# 9_arduinoConnectors.net
KiCad netlist of a schematic drawn in Altium Designer
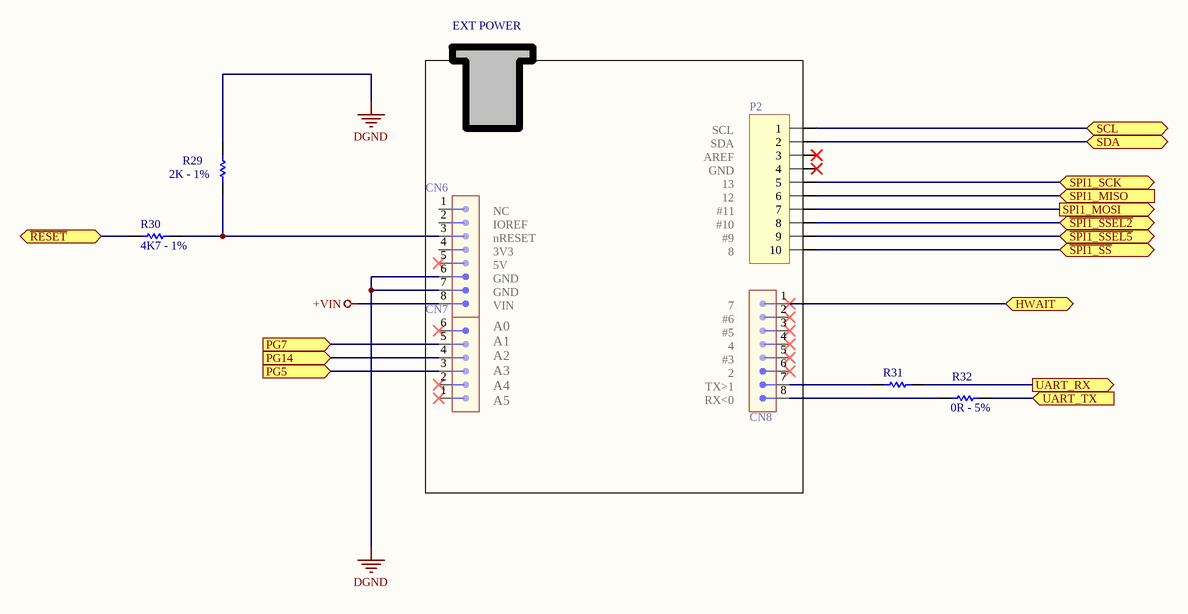
[diagram p0: 9_arduinoConnectors.SchDoc]

(export (version "E")
  (design (tool "Eeschema 10.0.6"))
  (components
    (comp (ref "CN6")
      (value "Conector M HEADER, 180G, SIMPLES, 8P")
      (footprint "BLKCON.100/MCS-8/W.100/8")
      (fields (field (name "MANUFACTURER") "METALTEX") (field (name "PARTNUMBER") "MCS-08"))
      (libsource (lib "") (part "CNC M HEADER, 180G, SIMPLES, 8P - 786_1"))
    )
    (comp (ref "CN7")
      (value "Conector M HEADER, 180G, SIMPLES, 6P")
      (footprint "BLKCON.100/MCS-6/W.100/6")
      (fields (field (name "MANUFACTURER") "METALTEX") (field (name "PARTNUMBER") "MCS-06"))
      (libsource (lib "Conector") (part "CNC M HEADER, 180G, SIMPLES, 6P - 785"))
    )
    (comp (ref "CN8")
      (value "Conector M HEADER, 180G, SIMPLES, 8P")
      (footprint "BLKCON.100/MCS-8/W.100/8")
      (fields (field (name "MANUFACTURER") "METALTEX") (field (name "PARTNUMBER") "MCS-08"))
      (libsource (lib "Conector") (part "CNC M HEADER, 180G, SIMPLES, 8P - 786"))
    )
    (comp (ref "P2")
      (value "Header 10")
      (footprint "HDR1X10")
      (description "Header, 10-Pin")
      (fields (field (name "PUBLISHER") "Altium Limited"))
      (libsource (lib "Miscellaneous Connectors") (part "Header 10"))
    )
    (comp (ref "R29")
      (value "2K - 1% - 0805 - 392")
      (footprint "SMD0805")
      (description "Resistor 2K, 1%, SMD 0805")
      (fields
        (field (name "PARTNUMBER") "0805W8F2001T5E")
        (field (name "MANUFACTURER") "SAMSUNG")
        (field (name "VALOR") "2K - 1%")
      )
      (libsource (lib "Resistor_smd") (part "2K - 1% - 0805 - 392"))
    )
    (comp (ref "R30")
      (value "4K7 - 1% - 0805 - 438")
      (footprint "SMD0805")
      (description "Resistor 4K7, 1%, SMD 0805")
      (fields
        (field (name "PARTNUMBER") "RC2012F4701CS")
        (field (name "MANUFACTURER") "SAMSUNG")
        (field (name "VALOR") "4K7 - 1%")
      )
      (libsource (lib "Resistor_smd") (part "4K7 - 1% - 0805 - 438"))
    )
    (comp (ref "R31")
      (value "0R - 5% - 0805 - 3365")
      (footprint "SMD0805")
      (description "Resistor 0R, 5%, SMD 0805")
      (fields (field (name "PARTNUMBER") "ERJ-6GEY0R00V") (field (name "MANUFACTURER") "PANASONIC"))
      (libsource (lib "Resistor_smd") (part "0R - 5% - 0805 - 3365"))
    )
    (comp (ref "R32")
      (value "0R - 5% - 0805 - 3365")
      (footprint "SMD0805")
      (description "Resistor 0R, 5%, SMD 0805")
      (fields
        (field (name "PARTNUMBER") "ERJ-6GEY0R00V")
        (field (name "MANUFACTURER") "PANASONIC")
        (field (name "VALOR") "0R - 5%")
      )
      (libsource (lib "Resistor_smd") (part "0R - 5% - 0805 - 3365"))
    )
  )
  (nets
    (net (code "1") (name "+VIN") (class "Default")
      (node (ref "CN6") (pin "8") (pinfunction "8_8") (pintype "passive"))
    )
    (net (code "2") (name "/HWAIT") (class "Default")
      (node (ref "CN8") (pin "1") (pinfunction "1_1") (pintype "passive+no_connect"))
    )
    (net (code "3") (name "/PG5") (class "Default")
      (node (ref "CN7") (pin "3") (pinfunction "3_3") (pintype "passive"))
    )
    (net (code "4") (name "/PG7") (class "Default")
      (node (ref "CN7") (pin "5") (pinfunction "5_5") (pintype "passive"))
    )
    (net (code "5") (name "/PG14") (class "Default")
      (node (ref "CN7") (pin "4") (pinfunction "4_4") (pintype "passive"))
    )
    (net (code "6") (name "/RESET") (class "Default")
      (node (ref "R30") (pin "1") (pinfunction "1_1") (pintype "passive"))
    )
    (net (code "7") (name "/SCL") (class "Default")
      (node (ref "P2") (pin "1") (pinfunction "1_1") (pintype "passive"))
    )
    (net (code "8") (name "/SDA") (class "Default")
      (node (ref "P2") (pin "2") (pinfunction "2_2") (pintype "passive"))
    )
    (net (code "9") (name "/SPI1_MISO") (class "Default")
      (node (ref "P2") (pin "6") (pinfunction "6_6") (pintype "passive"))
    )
    (net (code "10") (name "/SPI1_MOSI") (class "Default")
      (node (ref "P2") (pin "7") (pinfunction "7_7") (pintype "passive"))
    )
    (net (code "11") (name "/SPI1_SCK") (class "Default")
      (node (ref "P2") (pin "5") (pinfunction "5_5") (pintype "passive"))
    )
    (net (code "12") (name "/SPI1_SS") (class "Default")
      (node (ref "P2") (pin "10") (pinfunction "10_10") (pintype "passive"))
    )
    (net (code "13") (name "/SPI1_SSEL2") (class "Default")
      (node (ref "P2") (pin "8") (pinfunction "8_8") (pintype "passive"))
    )
    (net (code "14") (name "/SPI1_SSEL5") (class "Default")
      (node (ref "P2") (pin "9") (pinfunction "9_9") (pintype "passive"))
    )
    (net (code "15") (name "/UART_RX") (class "Default")
      (node (ref "R31") (pin "2") (pinfunction "2_2") (pintype "passive"))
    )
    (net (code "16") (name "/UART_TX") (class "Default")
      (node (ref "R32") (pin "2") (pinfunction "2_2") (pintype "passive"))
    )
    (net (code "17") (name "DGND") (class "Default")
      (node (ref "CN6") (pin "6") (pinfunction "6_6") (pintype "passive"))
      (node (ref "CN6") (pin "7") (pinfunction "7_7") (pintype "passive"))
      (node (ref "R29") (pin "2") (pinfunction "2_2") (pintype "passive"))
    )
    (net (code "18") (name "Net-(CN6-Pad3)") (class "Default")
      (node (ref "CN6") (pin "3") (pinfunction "3_3") (pintype "passive"))
      (node (ref "R29") (pin "1") (pinfunction "1_1") (pintype "passive"))
      (node (ref "R30") (pin "2") (pinfunction "2_2") (pintype "passive"))
    )
    (net (code "19") (name "Net-(CN8-Pad7)") (class "Default")
      (node (ref "CN8") (pin "7") (pinfunction "7_7") (pintype "passive"))
      (node (ref "R31") (pin "1") (pinfunction "1_1") (pintype "passive"))
    )
    (net (code "20") (name "Net-(CN8-Pad8)") (class "Default")
      (node (ref "CN8") (pin "8") (pinfunction "8_8") (pintype "passive"))
      (node (ref "R32") (pin "1") (pinfunction "1_1") (pintype "passive"))
    )
    (net (code "21") (name "unconnected-(CN6-Pad1)") (class "Default")
      (node (ref "CN6") (pin "1") (pinfunction "1_1") (pintype "passive"))
    )
    (net (code "22") (name "unconnected-(CN6-Pad2)") (class "Default")
      (node (ref "CN6") (pin "2") (pinfunction "2_2") (pintype "passive"))
    )
    (net (code "23") (name "unconnected-(CN6-Pad4)") (class "Default")
      (node (ref "CN6") (pin "4") (pinfunction "4_4") (pintype "passive"))
    )
    (net (code "24") (name "unconnected-(CN6-Pad5)") (class "Default")
      (node (ref "CN6") (pin "5") (pinfunction "5_5") (pintype "passive+no_connect"))
    )
    (net (code "25") (name "unconnected-(CN7-Pad1)") (class "Default")
      (node (ref "CN7") (pin "1") (pinfunction "1_1") (pintype "passive+no_connect"))
    )
    (net (code "26") (name "unconnected-(CN7-Pad2)") (class "Default")
      (node (ref "CN7") (pin "2") (pinfunction "2_2") (pintype "passive+no_connect"))
    )
    (net (code "27") (name "unconnected-(CN7-Pad6)") (class "Default")
      (node (ref "CN7") (pin "6") (pinfunction "6_6") (pintype "passive+no_connect"))
    )
    (net (code "28") (name "unconnected-(CN8-Pad2)") (class "Default")
      (node (ref "CN8") (pin "2") (pinfunction "2_2") (pintype "passive+no_connect"))
    )
    (net (code "29") (name "unconnected-(CN8-Pad3)") (class "Default")
      (node (ref "CN8") (pin "3") (pinfunction "3_3") (pintype "passive+no_connect"))
    )
    (net (code "30") (name "unconnected-(CN8-Pad4)") (class "Default")
      (node (ref "CN8") (pin "4") (pinfunction "4_4") (pintype "passive+no_connect"))
    )
    (net (code "31") (name "unconnected-(CN8-Pad5)") (class "Default")
      (node (ref "CN8") (pin "5") (pinfunction "5_5") (pintype "passive+no_connect"))
    )
    (net (code "32") (name "unconnected-(CN8-Pad6)") (class "Default")
      (node (ref "CN8") (pin "6") (pinfunction "6_6") (pintype "passive+no_connect"))
    )
    (net (code "33") (name "unconnected-(P2-Pad3)") (class "Default")
      (node (ref "P2") (pin "3") (pinfunction "3_3") (pintype "passive+no_connect"))
    )
    (net (code "34") (name "unconnected-(P2-Pad4)") (class "Default")
      (node (ref "P2") (pin "4") (pinfunction "4_4") (pintype "passive+no_connect"))
    )
  )
)
